# sencerMain2kai.net
KiCad netlist of a schematic drawn in EAGLE
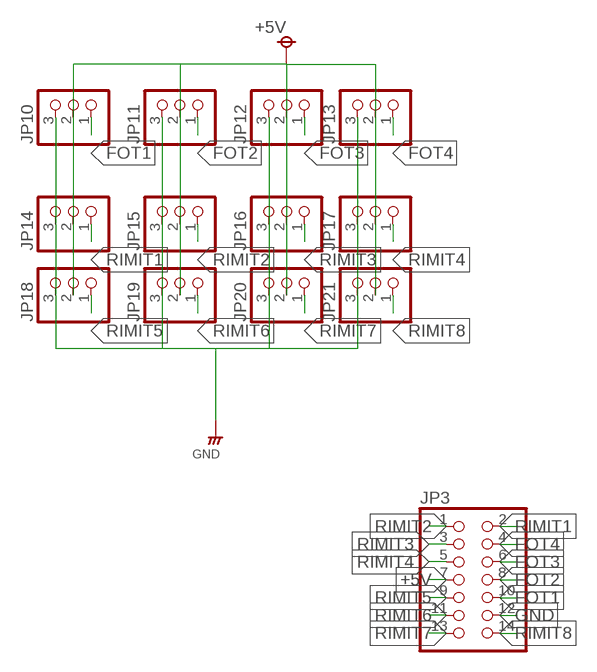
[diagram p0: schematic, sheet 1]

(export (version "E")
  (design (tool "Eeschema 10.0.6"))
  (components
    (comp (ref "JP3")
      (value "PINHD-2X7")
      (footprint "eagle-import:2X07")
      (libsource (lib "eagle-import") (part "PINHD-2X7"))
    )
    (comp (ref "JP10")
      (value "PINHD-1X3-1")
      (footprint "eagle-import:1_03")
      (libsource (lib "eagle-import") (part "PINHD-1X3-1"))
    )
    (comp (ref "JP11")
      (value "PINHD-1X3-1")
      (footprint "eagle-import:1_03")
      (libsource (lib "eagle-import") (part "PINHD-1X3-1"))
    )
    (comp (ref "JP12")
      (value "PINHD-1X3-1")
      (footprint "eagle-import:1_03")
      (libsource (lib "eagle-import") (part "PINHD-1X3-1"))
    )
    (comp (ref "JP13")
      (value "PINHD-1X3-1")
      (footprint "eagle-import:1_03")
      (libsource (lib "eagle-import") (part "PINHD-1X3-1"))
    )
    (comp (ref "JP14")
      (value "PINHD-1X3-1")
      (footprint "eagle-import:1_03")
      (libsource (lib "eagle-import") (part "PINHD-1X3-1"))
    )
    (comp (ref "JP15")
      (value "PINHD-1X3-1")
      (footprint "eagle-import:1_03")
      (libsource (lib "eagle-import") (part "PINHD-1X3-1"))
    )
    (comp (ref "JP16")
      (value "PINHD-1X3-1")
      (footprint "eagle-import:1_03")
      (libsource (lib "eagle-import") (part "PINHD-1X3-1"))
    )
    (comp (ref "JP17")
      (value "PINHD-1X3-1")
      (footprint "eagle-import:1_03")
      (libsource (lib "eagle-import") (part "PINHD-1X3-1"))
    )
    (comp (ref "JP18")
      (value "PINHD-1X3-1")
      (footprint "eagle-import:1_03")
      (libsource (lib "eagle-import") (part "PINHD-1X3-1"))
    )
    (comp (ref "JP19")
      (value "PINHD-1X3-1")
      (footprint "eagle-import:1_03")
      (libsource (lib "eagle-import") (part "PINHD-1X3-1"))
    )
    (comp (ref "JP20")
      (value "PINHD-1X3-1")
      (footprint "eagle-import:1_03")
      (libsource (lib "eagle-import") (part "PINHD-1X3-1"))
    )
    (comp (ref "JP21")
      (value "PINHD-1X3-1")
      (footprint "eagle-import:1_03")
      (libsource (lib "eagle-import") (part "PINHD-1X3-1"))
    )
  )
  (nets
    (net (code "1") (name "+5V") (class "Default")
      (node (ref "JP10") (pin "2") (pinfunction "2_2") (pintype "passive"))
      (node (ref "JP11") (pin "2") (pinfunction "2_2") (pintype "passive"))
      (node (ref "JP12") (pin "2") (pinfunction "2_2") (pintype "passive"))
      (node (ref "JP13") (pin "2") (pinfunction "2_2") (pintype "passive"))
      (node (ref "JP14") (pin "2") (pinfunction "2_2") (pintype "passive"))
      (node (ref "JP15") (pin "2") (pinfunction "2_2") (pintype "passive"))
      (node (ref "JP16") (pin "2") (pinfunction "2_2") (pintype "passive"))
      (node (ref "JP17") (pin "2") (pinfunction "2_2") (pintype "passive"))
      (node (ref "JP18") (pin "2") (pinfunction "2_2") (pintype "passive"))
      (node (ref "JP19") (pin "2") (pinfunction "2_2") (pintype "passive"))
      (node (ref "JP20") (pin "2") (pinfunction "2_2") (pintype "passive"))
      (node (ref "JP21") (pin "2") (pinfunction "2_2") (pintype "passive"))
      (node (ref "JP3") (pin "7") (pinfunction "7_7") (pintype "passive"))
    )
    (net (code "2") (name "FOT1") (class "Default")
      (node (ref "JP10") (pin "1") (pinfunction "3_1") (pintype "passive"))
      (node (ref "JP3") (pin "10") (pinfunction "10_10") (pintype "passive"))
    )
    (net (code "3") (name "FOT2") (class "Default")
      (node (ref "JP11") (pin "1") (pinfunction "3_1") (pintype "passive"))
      (node (ref "JP3") (pin "8") (pinfunction "8_8") (pintype "passive"))
    )
    (net (code "4") (name "FOT3") (class "Default")
      (node (ref "JP12") (pin "1") (pinfunction "3_1") (pintype "passive"))
      (node (ref "JP3") (pin "6") (pinfunction "6_6") (pintype "passive"))
    )
    (net (code "5") (name "FOT4") (class "Default")
      (node (ref "JP13") (pin "1") (pinfunction "3_1") (pintype "passive"))
      (node (ref "JP3") (pin "4") (pinfunction "4_4") (pintype "passive"))
    )
    (net (code "6") (name "GND") (class "Default")
      (node (ref "JP10") (pin "3") (pinfunction "1_3") (pintype "passive"))
      (node (ref "JP11") (pin "3") (pinfunction "1_3") (pintype "passive"))
      (node (ref "JP13") (pin "3") (pinfunction "1_3") (pintype "passive"))
      (node (ref "JP14") (pin "3") (pinfunction "1_3") (pintype "passive"))
      (node (ref "JP15") (pin "3") (pinfunction "1_3") (pintype "passive"))
      (node (ref "JP17") (pin "3") (pinfunction "1_3") (pintype "passive"))
      (node (ref "JP18") (pin "3") (pinfunction "1_3") (pintype "passive"))
      (node (ref "JP19") (pin "3") (pinfunction "1_3") (pintype "passive"))
      (node (ref "JP21") (pin "3") (pinfunction "1_3") (pintype "passive"))
      (node (ref "JP3") (pin "12") (pinfunction "12_12") (pintype "passive"))
    )
    (net (code "7") (name "Net-(JP12-1)") (class "Default")
      (node (ref "JP12") (pin "3") (pinfunction "1_3") (pintype "passive"))
      (node (ref "JP16") (pin "3") (pinfunction "1_3") (pintype "passive"))
      (node (ref "JP20") (pin "3") (pinfunction "1_3") (pintype "passive"))
    )
    (net (code "8") (name "RIMIT1") (class "Default")
      (node (ref "JP14") (pin "1") (pinfunction "3_1") (pintype "passive"))
      (node (ref "JP3") (pin "2") (pinfunction "2_2") (pintype "passive"))
    )
    (net (code "9") (name "RIMIT2") (class "Default")
      (node (ref "JP15") (pin "1") (pinfunction "3_1") (pintype "passive"))
      (node (ref "JP3") (pin "1") (pinfunction "1_1") (pintype "passive"))
    )
    (net (code "10") (name "RIMIT3") (class "Default")
      (node (ref "JP16") (pin "1") (pinfunction "3_1") (pintype "passive"))
      (node (ref "JP3") (pin "3") (pinfunction "3_3") (pintype "passive"))
    )
    (net (code "11") (name "RIMIT4") (class "Default")
      (node (ref "JP17") (pin "1") (pinfunction "3_1") (pintype "passive"))
      (node (ref "JP3") (pin "5") (pinfunction "5_5") (pintype "passive"))
    )
    (net (code "12") (name "RIMIT5") (class "Default")
      (node (ref "JP18") (pin "1") (pinfunction "3_1") (pintype "passive"))
      (node (ref "JP3") (pin "9") (pinfunction "9_9") (pintype "passive"))
    )
    (net (code "13") (name "RIMIT6") (class "Default")
      (node (ref "JP19") (pin "1") (pinfunction "3_1") (pintype "passive"))
      (node (ref "JP3") (pin "11") (pinfunction "11_11") (pintype "passive"))
    )
    (net (code "14") (name "RIMIT7") (class "Default")
      (node (ref "JP20") (pin "1") (pinfunction "3_1") (pintype "passive"))
      (node (ref "JP3") (pin "13") (pinfunction "13_13") (pintype "passive"))
    )
    (net (code "15") (name "RIMIT8") (class "Default")
      (node (ref "JP21") (pin "1") (pinfunction "3_1") (pintype "passive"))
      (node (ref "JP3") (pin "14") (pinfunction "14_14") (pintype "passive"))
    )
  )
)
